# demo_full.net
KiCad netlist of a schematic drawn in EAGLE
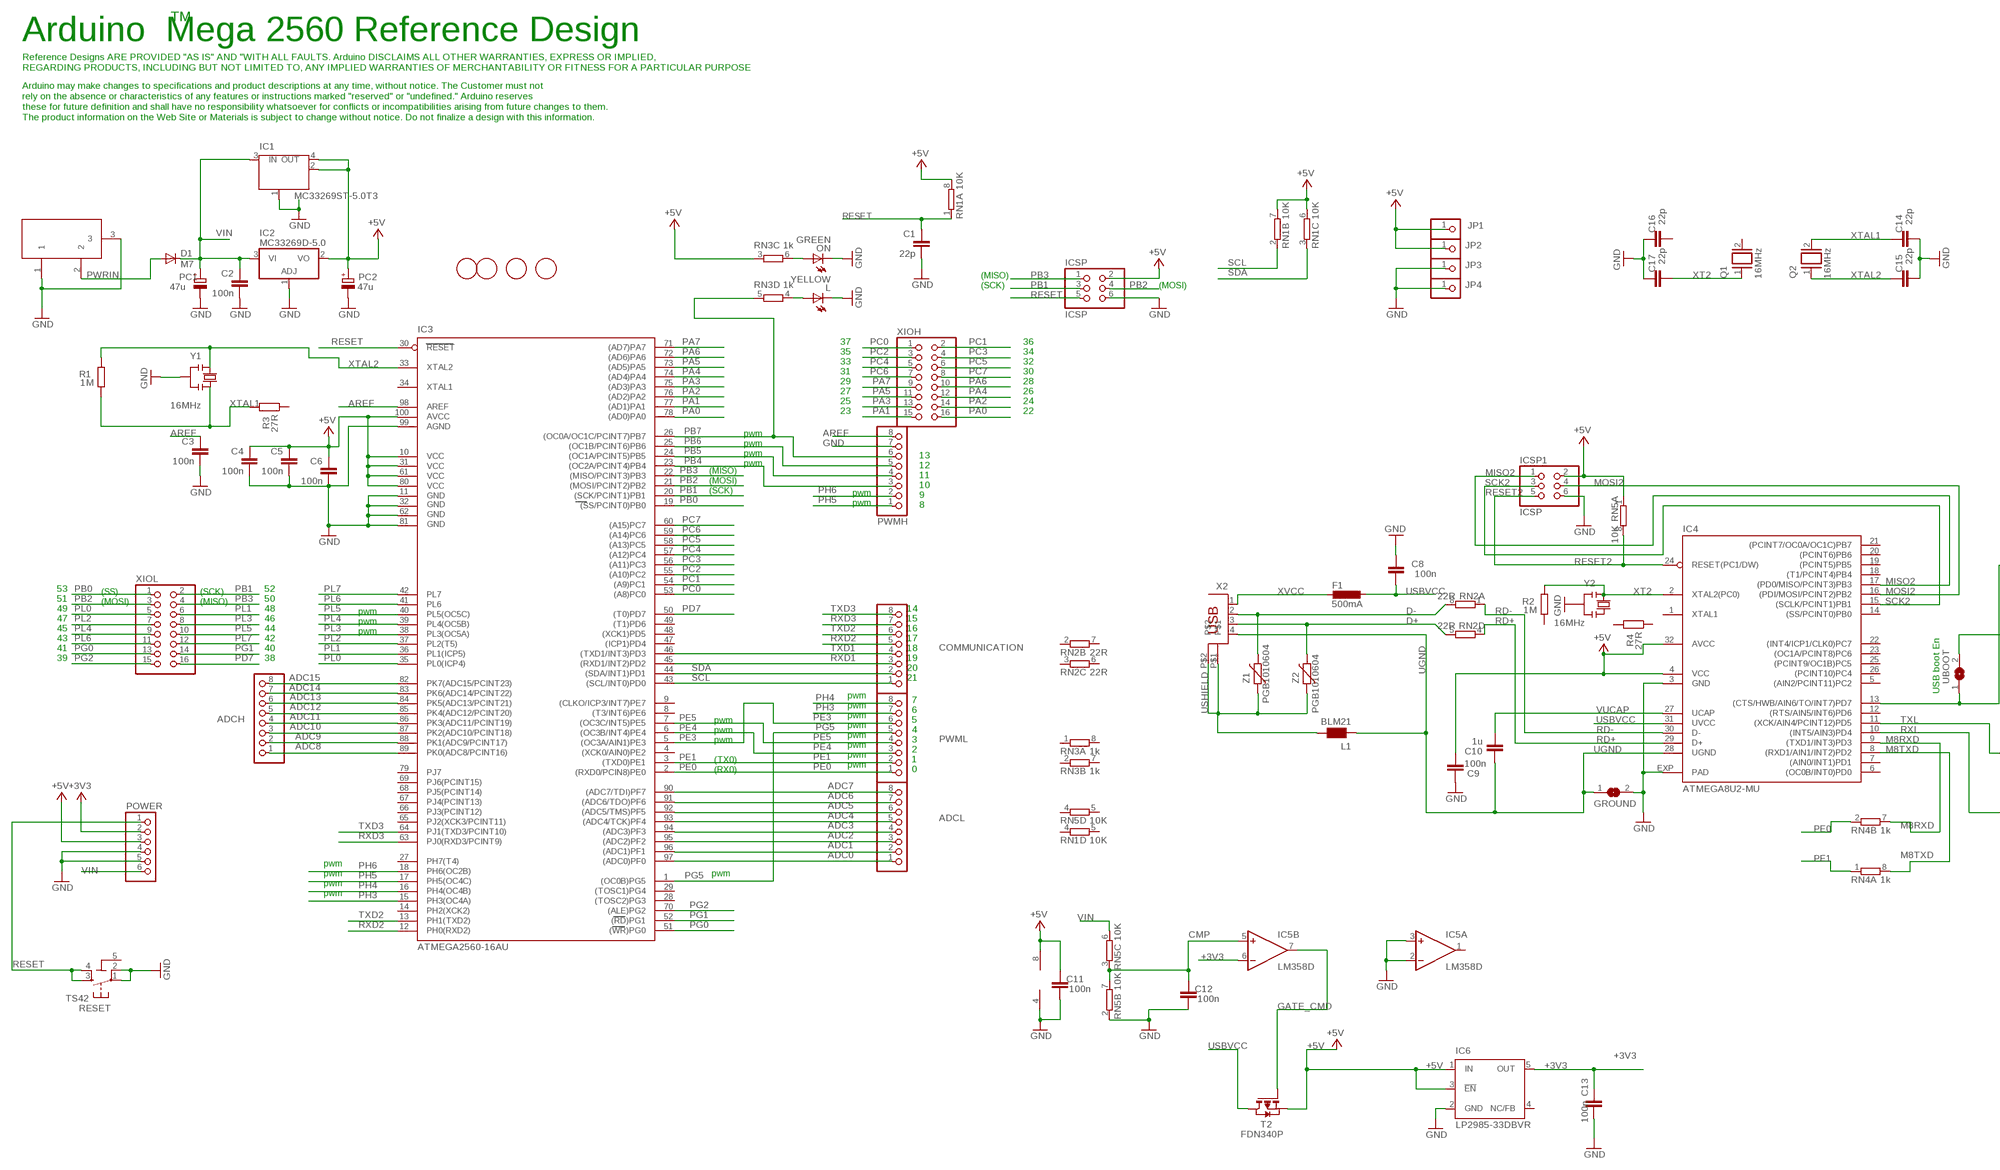
[diagram p0: schematic, sheet 1, part 1 of 2]
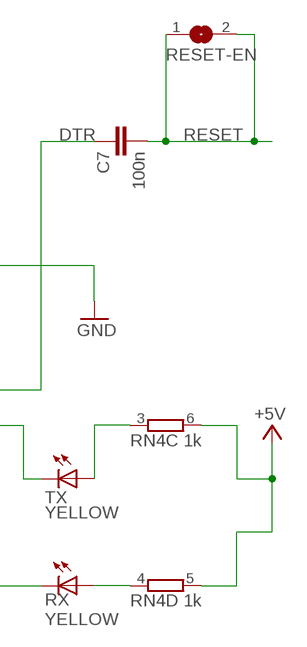
[diagram p1: schematic, sheet 1, part 2 of 2]

(export (version "E")
  (design (tool "Eeschema 10.0.6"))
  (components
    (comp (ref "ADCH")
      (value "PINHD-1X8")
      (footprint "eagle-import:1X08")
      (libsource (lib "eagle-import") (part "PINHD-1X8"))
    )
    (comp (ref "ADCL")
      (value "PINHD-1X8")
      (footprint "eagle-import:1X08")
      (libsource (lib "eagle-import") (part "PINHD-1X8"))
    )
    (comp (ref "C1")
      (value "22p")
      (footprint "eagle-import:C0603-ROUND")
      (libsource (lib "eagle-import") (part "C-EU0603-RND"))
    )
    (comp (ref "C2")
      (value "100n")
      (footprint "eagle-import:C0603-ROUND")
      (libsource (lib "eagle-import") (part "C-EU0603-RND"))
    )
    (comp (ref "C3")
      (value "100n")
      (footprint "eagle-import:C0603-ROUND")
      (libsource (lib "eagle-import") (part "C-EU0603-RND"))
    )
    (comp (ref "C4")
      (value "100n")
      (footprint "eagle-import:C0603-ROUND")
      (libsource (lib "eagle-import") (part "C-EU0603-RND"))
    )
    (comp (ref "C5")
      (value "100n")
      (footprint "eagle-import:C0603-ROUND")
      (libsource (lib "eagle-import") (part "C-EU0603-RND"))
    )
    (comp (ref "C6")
      (value "100n")
      (footprint "eagle-import:C0603-ROUND")
      (libsource (lib "eagle-import") (part "C-EU0603-RND"))
    )
    (comp (ref "C7")
      (value "100n")
      (footprint "eagle-import:C0603-ROUND")
      (libsource (lib "eagle-import") (part "C-EU0603-RND"))
    )
    (comp (ref "C8")
      (value "100n")
      (footprint "eagle-import:C0603")
      (libsource (lib "eagle-import") (part "rcl_C-EUC0603"))
    )
    (comp (ref "C9")
      (value "100n")
      (footprint "eagle-import:C0603-ROUND")
      (libsource (lib "eagle-import") (part "C-EU0603-RND"))
    )
    (comp (ref "C10")
      (value "1u")
      (footprint "eagle-import:C0603-ROUND")
      (libsource (lib "eagle-import") (part "C-EU0603-RND"))
    )
    (comp (ref "C11")
      (value "100n")
      (footprint "eagle-import:C0603")
      (libsource (lib "eagle-import") (part "rcl_C-EUC0603"))
    )
    (comp (ref "C12")
      (value "100n")
      (footprint "eagle-import:C0603-ROUND")
      (libsource (lib "eagle-import") (part "C-EU0603-RND"))
    )
    (comp (ref "C13")
      (value "100n")
      (footprint "eagle-import:C0603-ROUND")
      (libsource (lib "eagle-import") (part "C-EU0603-RND"))
    )
    (comp (ref "C14")
      (value "22p")
      (footprint "eagle-import:C0603-ROUND")
      (libsource (lib "eagle-import") (part "C-EU0603-RND"))
    )
    (comp (ref "C15")
      (value "22p")
      (footprint "eagle-import:C0603-ROUND")
      (libsource (lib "eagle-import") (part "C-EU0603-RND"))
    )
    (comp (ref "C16")
      (value "22p")
      (footprint "eagle-import:C0603-ROUND")
      (libsource (lib "eagle-import") (part "C-EU0603-RND"))
    )
    (comp (ref "C17")
      (value "22p")
      (footprint "eagle-import:C0603-ROUND")
      (libsource (lib "eagle-import") (part "C-EU0603-RND"))
    )
    (comp (ref "COMMUNICATION")
      (value "PINHD-1X8")
      (footprint "eagle-import:1X08")
      (libsource (lib "eagle-import") (part "PINHD-1X8"))
    )
    (comp (ref "D1")
      (value "M7")
      (footprint "eagle-import:SMB")
      (libsource (lib "eagle-import") (part "DIODE-SMB"))
    )
    (comp (ref "F1")
      (value "500mA")
      (footprint "eagle-import:L1812")
      (libsource (lib "eagle-import") (part "L-EUL1812"))
    )
    (comp (ref "GROUND")
      (value "SJ")
      (footprint "eagle-import:SJ")
      (libsource (lib "eagle-import") (part "SJ"))
    )
    (comp (ref "IC1")
      (value "MC33269ST-5.0T3")
      (footprint "eagle-import:SOT223")
      (libsource (lib "eagle-import") (part "MC33269ST-3.3T3"))
    )
    (comp (ref "IC2")
      (value "MC33269D-5.0")
      (footprint "eagle-import:DPACK")
      (libsource (lib "eagle-import") (part "MC33269?D-5.0"))
    )
    (comp (ref "IC3")
      (value "ATMEGA2560-16AU")
      (footprint "eagle-import:TQFP100")
      (libsource (lib "eagle-import") (part "ATMEGAAU1280-16"))
    )
    (comp (ref "IC4")
      (value "ATMEGA8U2-MU")
      (footprint "eagle-import:QFN32")
      (libsource (lib "eagle-import") (part "ATMEGA8U2-MU"))
    )
    (comp (ref "IC5")
      (value "LM358D")
      (footprint "eagle-import:SO08")
      (libsource (lib "eagle-import") (part "LM358D"))
    )
    (comp (ref "IC6")
      (value "LP2985-33DBVR")
      (footprint "eagle-import:SOT23-DBV")
      (libsource (lib "eagle-import") (part "TPS77033"))
    )
    (comp (ref "ICSP")
      (value "ICSP")
      (footprint "eagle-import:2X03")
      (libsource (lib "eagle-import") (part "PINHD-2X3"))
    )
    (comp (ref "ICSP1")
      (value "ICSP")
      (footprint "eagle-import:2X03")
      (libsource (lib "eagle-import") (part "PINHD-2X3"))
    )
    (comp (ref "JP1")
      (value "PINHD-1X1")
      (footprint "eagle-import:1X01")
      (libsource (lib "eagle-import") (part "PINHD-1X1"))
    )
    (comp (ref "JP2")
      (value "PINHD-1X1")
      (footprint "eagle-import:1X01")
      (libsource (lib "eagle-import") (part "PINHD-1X1"))
    )
    (comp (ref "JP3")
      (value "PINHD-1X1")
      (footprint "eagle-import:1X01")
      (libsource (lib "eagle-import") (part "PINHD-1X1"))
    )
    (comp (ref "JP4")
      (value "PINHD-1X1")
      (footprint "eagle-import:1X01")
      (libsource (lib "eagle-import") (part "PINHD-1X1"))
    )
    (comp (ref "L")
      (value "YELLOW")
      (footprint "eagle-import:CHIP-LED0805")
      (libsource (lib "eagle-import") (part "LEDCHIP-LED0805"))
    )
    (comp (ref "L1")
      (value "BLM21")
      (footprint "eagle-import:0805")
      (libsource (lib "eagle-import") (part "WE-CBF_0805"))
    )
    (comp (ref "ON")
      (value "GREEN")
      (footprint "eagle-import:CHIP-LED0805")
      (libsource (lib "eagle-import") (part "LEDCHIP-LED0805"))
    )
    (comp (ref "PC1")
      (value "47u")
      (footprint "eagle-import:PANASONIC_D")
      (libsource (lib "eagle-import") (part "CPOL-EUD"))
    )
    (comp (ref "PC2")
      (value "47u")
      (footprint "eagle-import:PANASONIC_D")
      (libsource (lib "eagle-import") (part "CPOL-EUD"))
    )
    (comp (ref "POWER")
      (value "PINHD-1X6")
      (footprint "eagle-import:1X06")
      (libsource (lib "eagle-import") (part "PINHD-1X6"))
    )
    (comp (ref "PWMH")
      (value "PINHD-1X8")
      (footprint "eagle-import:1X08")
      (libsource (lib "eagle-import") (part "PINHD-1X8"))
    )
    (comp (ref "PWML")
      (value "PINHD-1X8")
      (footprint "eagle-import:1X08")
      (libsource (lib "eagle-import") (part "PINHD-1X8"))
    )
    (comp (ref "Q1")
      (value "16MHz")
      (footprint "eagle-import:QS")
      (libsource (lib "eagle-import") (part "XTAL/S"))
    )
    (comp (ref "Q2")
      (value "16MHz")
      (footprint "eagle-import:QS")
      (libsource (lib "eagle-import") (part "XTAL/S"))
    )
    (comp (ref "R1")
      (value "1M")
      (footprint "eagle-import:R0603-ROUND")
      (libsource (lib "eagle-import") (part "R-EU_R0603"))
    )
    (comp (ref "R2")
      (value "1M")
      (footprint "eagle-import:R0603-ROUND")
      (libsource (lib "eagle-import") (part "R-EU_R0603"))
    )
    (comp (ref "R3")
      (value "27R")
      (footprint "eagle-import:R0603-ROUND")
      (libsource (lib "eagle-import") (part "R-EU_R0603"))
    )
    (comp (ref "R4")
      (value "27R")
      (footprint "eagle-import:R0603-ROUND")
      (libsource (lib "eagle-import") (part "R-EU_R0603"))
    )
    (comp (ref "RESET")
      (value "TS42")
      (footprint "eagle-import:TS42")
      (libsource (lib "eagle-import") (part "TS42"))
    )
    (comp (ref "RESET-EN")
      (value "SJ")
      (footprint "eagle-import:SJ")
      (libsource (lib "eagle-import") (part "SJ"))
    )
    (comp (ref "RN1")
      (value "10K")
      (footprint "eagle-import:CAT16")
      (libsource (lib "eagle-import") (part "4R-NCAT16"))
    )
    (comp (ref "RN2")
      (value "22R")
      (footprint "eagle-import:CAY16")
      (libsource (lib "eagle-import") (part "4R-NCAY16"))
    )
    (comp (ref "RN3")
      (value "1k")
      (footprint "eagle-import:CAY16")
      (libsource (lib "eagle-import") (part "4R-NCAY16"))
    )
    (comp (ref "RN4")
      (value "1k")
      (footprint "eagle-import:CAY16")
      (libsource (lib "eagle-import") (part "4R-NCAY16"))
    )
    (comp (ref "RN5")
      (value "10K")
      (footprint "eagle-import:CAT16")
      (libsource (lib "eagle-import") (part "4R-NCAT16"))
    )
    (comp (ref "RX")
      (value "YELLOW")
      (footprint "eagle-import:CHIP-LED0805")
      (libsource (lib "eagle-import") (part "LEDCHIP-LED0805"))
    )
    (comp (ref "T2")
      (value "FDN340P")
      (footprint "eagle-import:SOT-23")
      (libsource (lib "eagle-import") (part "PMOSSOT23"))
    )
    (comp (ref "TX")
      (value "YELLOW")
      (footprint "eagle-import:CHIP-LED0805")
      (libsource (lib "eagle-import") (part "LEDCHIP-LED0805"))
    )
    (comp (ref "U$2")
      (value "FIDUCIALMOUNT")
      (footprint "eagle-import:FIDUCIA-MOUNT")
      (libsource (lib "eagle-import") (part "FIDUCIALMOUNT"))
    )
    (comp (ref "U$3")
      (value "FIDUCIALMOUNT")
      (footprint "eagle-import:FIDUCIA-MOUNT")
      (libsource (lib "eagle-import") (part "FIDUCIALMOUNT"))
    )
    (comp (ref "U$4")
      (value "FIDUCIALMOUNT")
      (footprint "eagle-import:FIDUCIA-MOUNT")
      (libsource (lib "eagle-import") (part "FIDUCIALMOUNT"))
    )
    (comp (ref "U$5")
      (value "FIDUCIALMOUNT")
      (footprint "eagle-import:FIDUCIA-MOUNT")
      (libsource (lib "eagle-import") (part "FIDUCIALMOUNT"))
    )
    (comp (ref "UBOOT")
      (value "SJ")
      (footprint "eagle-import:SJ")
      (libsource (lib "eagle-import") (part "SJ"))
    )
    (comp (ref "X1")
      (value "DC21MMX")
      (footprint "eagle-import:DC-21MM")
      (libsource (lib "eagle-import") (part "DC21MMX"))
    )
    (comp (ref "X2")
      (value "PN61729")
      (footprint "eagle-import:PN61729")
      (libsource (lib "eagle-import") (part "PN61729"))
    )
    (comp (ref "XIOH")
      (value "PINHD-2X8")
      (footprint "eagle-import:2X08")
      (libsource (lib "eagle-import") (part "PINHD-2X8"))
    )
    (comp (ref "XIOL")
      (value "PINHD-2X8")
      (footprint "eagle-import:2X08")
      (libsource (lib "eagle-import") (part "PINHD-2X8"))
    )
    (comp (ref "Y1")
      (value "16MHz")
      (footprint "eagle-import:RESONATOR")
      (libsource (lib "eagle-import") (part "RESONATORMU"))
    )
    (comp (ref "Y2")
      (value "16MHz")
      (footprint "eagle-import:RESONATOR")
      (libsource (lib "eagle-import") (part "RESONATORMU"))
    )
    (comp (ref "Z1")
      (value "PGB1010604")
      (footprint "eagle-import:CT_CN0603")
      (libsource (lib "eagle-import") (part "VARISTORCN0603"))
    )
    (comp (ref "Z2")
      (value "PGB1010604")
      (footprint "eagle-import:CT_CN0603")
      (libsource (lib "eagle-import") (part "VARISTORCN0603"))
    )
  )
  (nets
    (net (code "1") (name "+3V3") (class "Default")
      (node (ref "C13") (pin "2") (pinfunction "2_2") (pintype "passive"))
      (node (ref "IC5") (pin "6") (pinfunction "-IN_6") (pintype "input"))
      (node (ref "IC6") (pin "5") (pinfunction "OUT_5") (pintype "passive"))
      (node (ref "POWER") (pin "2") (pinfunction "2_2") (pintype "passive"))
    )
    (net (code "2") (name "+5V") (class "Default")
      (node (ref "C11") (pin "2") (pinfunction "2_2") (pintype "passive"))
      (node (ref "C4") (pin "1") (pinfunction "1_1") (pintype "passive"))
      (node (ref "C5") (pin "1") (pinfunction "1_1") (pintype "passive"))
      (node (ref "C6") (pin "1") (pinfunction "1_1") (pintype "passive"))
      (node (ref "C9") (pin "1") (pinfunction "1_1") (pintype "passive"))
      (node (ref "IC1") (pin "2") (pinfunction "OUT_2") (pintype "passive"))
      (node (ref "IC1") (pin "4") (pinfunction "OUT_4") (pintype "passive"))
      (node (ref "IC2") (pin "2") (pinfunction "VO_2") (pintype "passive"))
      (node (ref "IC3") (pin "10") (pinfunction "VCC_10") (pintype "power_in"))
      (node (ref "IC3") (pin "100") (pinfunction "AVCC_100") (pintype "power_in"))
      (node (ref "IC3") (pin "31") (pinfunction "VCC1_31") (pintype "power_in"))
      (node (ref "IC3") (pin "61") (pinfunction "VCC2_61") (pintype "power_in"))
      (node (ref "IC3") (pin "80") (pinfunction "VCC3_80") (pintype "power_in"))
      (node (ref "IC4") (pin "32") (pinfunction "AVCC_32") (pintype "power_in"))
      (node (ref "IC4") (pin "4") (pinfunction "VCC_4") (pintype "power_in"))
      (node (ref "IC5") (pin "8") (pinfunction "V+_8") (pintype "power_in"))
      (node (ref "IC6") (pin "1") (pinfunction "IN_1") (pintype "input"))
      (node (ref "IC6") (pin "3") (pinfunction "~{EN}_3") (pintype "input"))
      (node (ref "ICSP") (pin "2") (pinfunction "2_2") (pintype "passive"))
      (node (ref "ICSP1") (pin "2") (pinfunction "2_2") (pintype "passive"))
      (node (ref "JP1") (pin "1") (pinfunction "1_1") (pintype "passive"))
      (node (ref "JP2") (pin "1") (pinfunction "1_1") (pintype "passive"))
      (node (ref "PC2") (pin "+") (pinfunction "+_+") (pintype "passive"))
      (node (ref "POWER") (pin "3") (pinfunction "3_3") (pintype "passive"))
      (node (ref "RN1") (pin "6") (pinfunction "2_6") (pintype "passive"))
      (node (ref "RN1") (pin "7") (pinfunction "2_7") (pintype "passive"))
      (node (ref "RN1") (pin "8") (pinfunction "2_8") (pintype "passive"))
      (node (ref "RN3") (pin "3") (pinfunction "1_3") (pintype "passive"))
      (node (ref "RN4") (pin "5") (pinfunction "2_5") (pintype "passive"))
      (node (ref "RN4") (pin "6") (pinfunction "2_6") (pintype "passive"))
      (node (ref "RN5") (pin "1") (pinfunction "1_1") (pintype "passive"))
      (node (ref "T2") (pin "2") (pinfunction "S_2") (pintype "passive"))
    )
    (net (code "3") (name "/5-GND") (class "Default")
      (node (ref "RESET") (pin "5") (pinfunction "5-GND_5") (pintype "power_in"))
    )
    (net (code "4") (name "/ADC0") (class "Default")
      (node (ref "ADCL") (pin "1") (pinfunction "1_1") (pintype "passive"))
      (node (ref "IC3") (pin "97") (pinfunction "(ADC0)PF0_97") (pintype "bidirectional"))
    )
    (net (code "5") (name "/ADC1") (class "Default")
      (node (ref "ADCL") (pin "2") (pinfunction "2_2") (pintype "passive"))
      (node (ref "IC3") (pin "96") (pinfunction "(ADC1)PF1_96") (pintype "bidirectional"))
    )
    (net (code "6") (name "/ADC2") (class "Default")
      (node (ref "ADCL") (pin "3") (pinfunction "3_3") (pintype "passive"))
      (node (ref "IC3") (pin "95") (pinfunction "(ADC2)PF2_95") (pintype "bidirectional"))
    )
    (net (code "7") (name "/ADC3") (class "Default")
      (node (ref "ADCL") (pin "4") (pinfunction "4_4") (pintype "passive"))
      (node (ref "IC3") (pin "94") (pinfunction "(ADC3)PF3_94") (pintype "bidirectional"))
    )
    (net (code "8") (name "/ADC4") (class "Default")
      (node (ref "ADCL") (pin "5") (pinfunction "5_5") (pintype "passive"))
      (node (ref "IC3") (pin "93") (pinfunction "(ADC4/TCK)PF4_93") (pintype "bidirectional"))
    )
    (net (code "9") (name "/ADC5") (class "Default")
      (node (ref "ADCL") (pin "6") (pinfunction "6_6") (pintype "passive"))
      (node (ref "IC3") (pin "92") (pinfunction "(ADC5/TMS)PF5_92") (pintype "bidirectional"))
    )
    (net (code "10") (name "/ADC6") (class "Default")
      (node (ref "ADCL") (pin "7") (pinfunction "7_7") (pintype "passive"))
      (node (ref "IC3") (pin "91") (pinfunction "(ADC6/TDO)PF6_91") (pintype "bidirectional"))
    )
    (net (code "11") (name "/ADC7") (class "Default")
      (node (ref "ADCL") (pin "8") (pinfunction "8_8") (pintype "passive"))
      (node (ref "IC3") (pin "90") (pinfunction "(ADC7/TDI)PF7_90") (pintype "bidirectional"))
    )
    (net (code "12") (name "/ADC8") (class "Default")
      (node (ref "ADCH") (pin "1") (pinfunction "1_1") (pintype "passive"))
      (node (ref "IC3") (pin "89") (pinfunction "PK0(ADC8/PCINT16)_89") (pintype "bidirectional"))
    )
    (net (code "13") (name "/ADC9") (class "Default")
      (node (ref "ADCH") (pin "2") (pinfunction "2_2") (pintype "passive"))
      (node (ref "IC3") (pin "88") (pinfunction "PK1(ADC9/PCINT17)_88") (pintype "bidirectional"))
    )
    (net (code "14") (name "/ADC10") (class "Default")
      (node (ref "ADCH") (pin "3") (pinfunction "3_3") (pintype "passive"))
      (node (ref "IC3") (pin "87") (pinfunction "PK2(ADC10/PCINT18)_87") (pintype "bidirectional"))
    )
    (net (code "15") (name "/ADC11") (class "Default")
      (node (ref "ADCH") (pin "4") (pinfunction "4_4") (pintype "passive"))
      (node (ref "IC3") (pin "86") (pinfunction "PK3(ADC11/PCINT19)_86") (pintype "bidirectional"))
    )
    (net (code "16") (name "/ADC12") (class "Default")
      (node (ref "ADCH") (pin "5") (pinfunction "5_5") (pintype "passive"))
      (node (ref "IC3") (pin "85") (pinfunction "PK4(ADC12/PCINT20)_85") (pintype "bidirectional"))
    )
    (net (code "17") (name "/ADC13") (class "Default")
      (node (ref "ADCH") (pin "6") (pinfunction "6_6") (pintype "passive"))
      (node (ref "IC3") (pin "84") (pinfunction "PK5(ADC13/PCINT21)_84") (pintype "bidirectional"))
    )
    (net (code "18") (name "/ADC14") (class "Default")
      (node (ref "ADCH") (pin "7") (pinfunction "7_7") (pintype "passive"))
      (node (ref "IC3") (pin "83") (pinfunction "PK6(ADC14/PCINT22)_83") (pintype "bidirectional"))
    )
    (net (code "19") (name "/ADC15") (class "Default")
      (node (ref "ADCH") (pin "8") (pinfunction "8_8") (pintype "passive"))
      (node (ref "IC3") (pin "82") (pinfunction "PK7(ADC15/PCINT23)_82") (pintype "bidirectional"))
    )
    (net (code "20") (name "/AREF") (class "Default")
      (node (ref "C3") (pin "1") (pinfunction "1_1") (pintype "passive"))
      (node (ref "IC3") (pin "98") (pinfunction "AREF_98") (pintype "bidirectional"))
      (node (ref "PWMH") (pin "8") (pinfunction "8_8") (pintype "passive"))
    )
    (net (code "21") (name "/CMP") (class "Default")
      (node (ref "C12") (pin "2") (pinfunction "2_2") (pintype "passive"))
      (node (ref "IC5") (pin "5") (pinfunction "+IN_5") (pintype "input"))
      (node (ref "RN5") (pin "3") (pinfunction "1_3") (pintype "passive"))
      (node (ref "RN5") (pin "7") (pinfunction "2_7") (pintype "passive"))
    )
    (net (code "22") (name "/D+") (class "Default")
      (node (ref "RN2") (pin "5") (pinfunction "2_5") (pintype "passive"))
      (node (ref "X2") (pin "3") (pinfunction "3_3") (pintype "bidirectional"))
      (node (ref "Z2") (pin "2") (pinfunction "2_2") (pintype "passive"))
    )
    (net (code "23") (name "/D-") (class "Default")
      (node (ref "RN2") (pin "8") (pinfunction "2_8") (pintype "passive"))
      (node (ref "X2") (pin "2") (pinfunction "2_2") (pintype "bidirectional"))
      (node (ref "Z1") (pin "2") (pinfunction "2_2") (pintype "passive"))
    )
    (net (code "24") (name "/DTR") (class "Default")
      (node (ref "C7") (pin "1") (pinfunction "1_1") (pintype "passive"))
      (node (ref "IC4") (pin "13") (pinfunction "(CTS/HWB/AIN6/TO/INT7)PD7_13") (pintype "bidirectional"))
      (node (ref "UBOOT") (pin "1") (pinfunction "1_1") (pintype "passive"))
    )
    (net (code "25") (name "/GATE_CMD") (class "Default")
      (node (ref "IC5") (pin "7") (pinfunction "OUT_7") (pintype "output"))
      (node (ref "T2") (pin "3") (pinfunction "G_3") (pintype "passive"))
    )
    (net (code "26") (name "/M8RXD") (class "Default")
      (node (ref "IC4") (pin "9") (pinfunction "(TXD1/INT3)PD3_9") (pintype "bidirectional"))
      (node (ref "RN4") (pin "7") (pinfunction "2_7") (pintype "passive"))
    )
    (net (code "27") (name "/M8TXD") (class "Default")
      (node (ref "IC4") (pin "8") (pinfunction "(RXD1/AIN1/INT2)PD2_8") (pintype "bidirectional"))
      (node (ref "RN4") (pin "8") (pinfunction "2_8") (pintype "passive"))
    )
    (net (code "28") (name "/MISO2") (class "Default")
      (node (ref "IC4") (pin "17") (pinfunction "(PD0/MISO/PCINT3)PB3_17") (pintype "bidirectional"))
      (node (ref "ICSP1") (pin "1") (pinfunction "1_1") (pintype "passive"))
    )
    (net (code "29") (name "/MOSI2") (class "Default")
      (node (ref "IC4") (pin "16") (pinfunction "(PDI/MOSI/PCINT2)PB2_16") (pintype "bidirectional"))
      (node (ref "ICSP1") (pin "4") (pinfunction "4_4") (pintype "passive"))
    )
    (net (code "30") (name "/PA0") (class "Default")
      (node (ref "IC3") (pin "78") (pinfunction "(AD0)PA0_78") (pintype "bidirectional"))
      (node (ref "XIOH") (pin "16") (pinfunction "16_16") (pintype "passive"))
    )
    (net (code "31") (name "/PA1") (class "Default")
      (node (ref "IC3") (pin "77") (pinfunction "(AD1)PA1_77") (pintype "bidirectional"))
      (node (ref "XIOH") (pin "15") (pinfunction "15_15") (pintype "passive"))
    )
    (net (code "32") (name "/PA2") (class "Default")
      (node (ref "IC3") (pin "76") (pinfunction "(AD2)PA2_76") (pintype "bidirectional"))
      (node (ref "XIOH") (pin "14") (pinfunction "14_14") (pintype "passive"))
    )
    (net (code "33") (name "/PA3") (class "Default")
      (node (ref "IC3") (pin "75") (pinfunction "(AD3)PA3_75") (pintype "bidirectional"))
      (node (ref "XIOH") (pin "13") (pinfunction "13_13") (pintype "passive"))
    )
    (net (code "34") (name "/PA4") (class "Default")
      (node (ref "IC3") (pin "74") (pinfunction "(AD4)PA4_74") (pintype "bidirectional"))
      (node (ref "XIOH") (pin "12") (pinfunction "12_12") (pintype "passive"))
    )
    (net (code "35") (name "/PA5") (class "Default")
      (node (ref "IC3") (pin "73") (pinfunction "(AD5)PA5_73") (pintype "bidirectional"))
      (node (ref "XIOH") (pin "11") (pinfunction "11_11") (pintype "passive"))
    )
    (net (code "36") (name "/PA6") (class "Default")
      (node (ref "IC3") (pin "72") (pinfunction "(AD6)PA6_72") (pintype "bidirectional"))
      (node (ref "XIOH") (pin "10") (pinfunction "10_10") (pintype "passive"))
    )
    (net (code "37") (name "/PA7") (class "Default")
      (node (ref "IC3") (pin "71") (pinfunction "(AD7)PA7_71") (pintype "bidirectional"))
      (node (ref "XIOH") (pin "9") (pinfunction "9_9") (pintype "passive"))
    )
    (net (code "38") (name "/PB0") (class "Default")
      (node (ref "IC3") (pin "19") (pinfunction "(SS/PCINT0)PB0_19") (pintype "bidirectional"))
      (node (ref "XIOL") (pin "1") (pinfunction "1_1") (pintype "passive"))
    )
    (net (code "39") (name "/PB1") (class "Default")
      (node (ref "IC3") (pin "20") (pinfunction "(SCK/PCINT1)PB1_20") (pintype "bidirectional"))
      (node (ref "ICSP") (pin "3") (pinfunction "3_3") (pintype "passive"))
      (node (ref "XIOL") (pin "2") (pinfunction "2_2") (pintype "passive"))
    )
    (net (code "40") (name "/PB2") (class "Default")
      (node (ref "IC3") (pin "21") (pinfunction "(MOSI/PCINT2)PB2_21") (pintype "bidirectional"))
      (node (ref "ICSP") (pin "4") (pinfunction "4_4") (pintype "passive"))
      (node (ref "XIOL") (pin "3") (pinfunction "3_3") (pintype "passive"))
    )
    (net (code "41") (name "/PB3") (class "Default")
      (node (ref "IC3") (pin "22") (pinfunction "(MISO/PCINT3)PB3_22") (pintype "bidirectional"))
      (node (ref "ICSP") (pin "1") (pinfunction "1_1") (pintype "passive"))
      (node (ref "XIOL") (pin "4") (pinfunction "4_4") (pintype "passive"))
    )
    (net (code "42") (name "/PB4") (class "Default")
      (node (ref "IC3") (pin "23") (pinfunction "(OC2A/PCINT4)PB4_23") (pintype "bidirectional"))
      (node (ref "PWMH") (pin "3") (pinfunction "3_3") (pintype "passive"))
    )
    (net (code "43") (name "/PB5") (class "Default")
      (node (ref "IC3") (pin "24") (pinfunction "(OC1A/PCINT5)PB5_24") (pintype "bidirectional"))
      (node (ref "PWMH") (pin "4") (pinfunction "4_4") (pintype "passive"))
    )
    (net (code "44") (name "/PB6") (class "Default")
      (node (ref "IC3") (pin "25") (pinfunction "(OC1B/PCINT6)PB6_25") (pintype "bidirectional"))
      (node (ref "PWMH") (pin "5") (pinfunction "5_5") (pintype "passive"))
    )
    (net (code "45") (name "/PB7") (class "Default")
      (node (ref "IC3") (pin "26") (pinfunction "(OC0A/OC1C/PCINT7)PB7_26") (pintype "bidirectional"))
      (node (ref "PWMH") (pin "6") (pinfunction "6_6") (pintype "passive"))
      (node (ref "RN3") (pin "5") (pinfunction "2_5") (pintype "passive"))
    )
    (net (code "46") (name "/PC0") (class "Default")
      (node (ref "IC3") (pin "53") (pinfunction "(A8)PC0_53") (pintype "bidirectional"))
      (node (ref "XIOH") (pin "1") (pinfunction "1_1") (pintype "passive"))
    )
    (net (code "47") (name "/PC1") (class "Default")
      (node (ref "IC3") (pin "54") (pinfunction "(A9)PC1_54") (pintype "bidirectional"))
      (node (ref "XIOH") (pin "2") (pinfunction "2_2") (pintype "passive"))
    )
    (net (code "48") (name "/PC2") (class "Default")
      (node (ref "IC3") (pin "55") (pinfunction "(A10)PC2_55") (pintype "bidirectional"))
      (node (ref "XIOH") (pin "3") (pinfunction "3_3") (pintype "passive"))
    )
    (net (code "49") (name "/PC3") (class "Default")
      (node (ref "IC3") (pin "56") (pinfunction "(A11)PC3_56") (pintype "bidirectional"))
      (node (ref "XIOH") (pin "4") (pinfunction "4_4") (pintype "passive"))
    )
    (net (code "50") (name "/PC4") (class "Default")
      (node (ref "IC3") (pin "57") (pinfunction "(A12)PC4_57") (pintype "bidirectional"))
      (node (ref "XIOH") (pin "5") (pinfunction "5_5") (pintype "passive"))
    )
    (net (code "51") (name "/PC5") (class "Default")
      (node (ref "IC3") (pin "58") (pinfunction "(A13)PC5_58") (pintype "bidirectional"))
      (node (ref "XIOH") (pin "6") (pinfunction "6_6") (pintype "passive"))
    )
    (net (code "52") (name "/PC6") (class "Default")
      (node (ref "IC3") (pin "59") (pinfunction "(A14)PC6_59") (pintype "bidirectional"))
      (node (ref "XIOH") (pin "7") (pinfunction "7_7") (pintype "passive"))
    )
    (net (code "53") (name "/PC7") (class "Default")
      (node (ref "IC3") (pin "60") (pinfunction "(A15)PC7_60") (pintype "bidirectional"))
      (node (ref "XIOH") (pin "8") (pinfunction "8_8") (pintype "passive"))
    )
    (net (code "54") (name "/PD7") (class "Default")
      (node (ref "IC3") (pin "50") (pinfunction "(T0)PD7_50") (pintype "bidirectional"))
      (node (ref "XIOL") (pin "16") (pinfunction "16_16") (pintype "passive"))
    )
    (net (code "55") (name "/PE0") (class "Default")
      (node (ref "IC3") (pin "2") (pinfunction "(RXD0/PCIN8)PE0_2") (pintype "bidirectional"))
      (node (ref "PWML") (pin "1") (pinfunction "1_1") (pintype "passive"))
      (node (ref "RN4") (pin "2") (pinfunction "1_2") (pintype "passive"))
    )
    (net (code "56") (name "/PE1") (class "Default")
      (node (ref "IC3") (pin "3") (pinfunction "(TXD0)PE1_3") (pintype "bidirectional"))
      (node (ref "PWML") (pin "2") (pinfunction "2_2") (pintype "passive"))
      (node (ref "RN4") (pin "1") (pinfunction "1_1") (pintype "passive"))
    )
    (net (code "57") (name "/PE3") (class "Default")
      (node (ref "IC3") (pin "5") (pinfunction "(OC3A/AIN1)PE3_5") (pintype "bidirectional"))
      (node (ref "PWML") (pin "6") (pinfunction "6_6") (pintype "passive"))
    )
    (net (code "58") (name "/PE4") (class "Default")
      (node (ref "IC3") (pin "6") (pinfunction "(OC3B/INT4)PE4_6") (pintype "bidirectional"))
      (node (ref "PWML") (pin "3") (pinfunction "3_3") (pintype "passive"))
    )
    (net (code "59") (name "/PE5") (class "Default")
      (node (ref "IC3") (pin "7") (pinfunction "(OC3C/INT5)PE5_7") (pintype "bidirectional"))
      (node (ref "PWML") (pin "4") (pinfunction "4_4") (pintype "passive"))
    )
    (net (code "60") (name "/PG0") (class "Default")
      (node (ref "IC3") (pin "51") (pinfunction "(WR)PG0_51") (pintype "bidirectional"))
      (node (ref "XIOL") (pin "13") (pinfunction "13_13") (pintype "passive"))
    )
    (net (code "61") (name "/PG1") (class "Default")
      (node (ref "IC3") (pin "52") (pinfunction "(RD)PG1_52") (pintype "bidirectional"))
      (node (ref "XIOL") (pin "14") (pinfunction "14_14") (pintype "passive"))
    )
    (net (code "62") (name "/PG2") (class "Default")
      (node (ref "IC3") (pin "70") (pinfunction "(ALE)PG2_70") (pintype "bidirectional"))
      (node (ref "XIOL") (pin "15") (pinfunction "15_15") (pintype "passive"))
    )
    (net (code "63") (name "/PG5") (class "Default")
      (node (ref "IC3") (pin "1") (pinfunction "(OC0B)PG5_1") (pintype "bidirectional"))
      (node (ref "PWML") (pin "5") (pinfunction "5_5") (pintype "passive"))
    )
    (net (code "64") (name "/PH3") (class "Default")
      (node (ref "IC3") (pin "15") (pinfunction "PH3(OC4A)_15") (pintype "bidirectional"))
      (node (ref "PWML") (pin "7") (pinfunction "7_7") (pintype "passive"))
    )
    (net (code "65") (name "/PH4") (class "Default")
      (node (ref "IC3") (pin "16") (pinfunction "PH4(OC4B)_16") (pintype "bidirectional"))
      (node (ref "PWML") (pin "8") (pinfunction "8_8") (pintype "passive"))
    )
    (net (code "66") (name "/PH5") (class "Default")
      (node (ref "IC3") (pin "17") (pinfunction "PH5(OC4C)_17") (pintype "bidirectional"))
      (node (ref "PWMH") (pin "1") (pinfunction "1_1") (pintype "passive"))
    )
    (net (code "67") (name "/PH6") (class "Default")
      (node (ref "IC3") (pin "18") (pinfunction "PH6(OC2B)_18") (pintype "bidirectional"))
      (node (ref "PWMH") (pin "2") (pinfunction "2_2") (pintype "passive"))
    )
    (net (code "68") (name "/PL0") (class "Default")
      (node (ref "IC3") (pin "35") (pinfunction "PL0(ICP4)_35") (pintype "bidirectional"))
      (node (ref "XIOL") (pin "5") (pinfunction "5_5") (pintype "passive"))
    )
    (net (code "69") (name "/PL1") (class "Default")
      (node (ref "IC3") (pin "36") (pinfunction "PL1(ICP5)_36") (pintype "bidirectional"))
      (node (ref "XIOL") (pin "6") (pinfunction "6_6") (pintype "passive"))
    )
    (net (code "70") (name "/PL2") (class "Default")
      (node (ref "IC3") (pin "37") (pinfunction "PL2(T5)_37") (pintype "bidirectional"))
      (node (ref "XIOL") (pin "7") (pinfunction "7_7") (pintype "passive"))
    )
    (net (code "71") (name "/PL3") (class "Default")
      (node (ref "IC3") (pin "38") (pinfunction "PL3(OC5A)_38") (pintype "bidirectional"))
      (node (ref "XIOL") (pin "8") (pinfunction "8_8") (pintype "passive"))
    )
    (net (code "72") (name "/PL4") (class "Default")
      (node (ref "IC3") (pin "39") (pinfunction "PL4(OC5B)_39") (pintype "bidirectional"))
      (node (ref "XIOL") (pin "9") (pinfunction "9_9") (pintype "passive"))
    )
    (net (code "73") (name "/PL5") (class "Default")
      (node (ref "IC3") (pin "40") (pinfunction "PL5(OC5C)_40") (pintype "bidirectional"))
      (node (ref "XIOL") (pin "10") (pinfunction "10_10") (pintype "passive"))
    )
    (net (code "74") (name "/PL6") (class "Default")
      (node (ref "IC3") (pin "41") (pinfunction "PL6_41") (pintype "bidirectional"))
      (node (ref "XIOL") (pin "11") (pinfunction "11_11") (pintype "passive"))
    )
    (net (code "75") (name "/PL7") (class "Default")
      (node (ref "IC3") (pin "42") (pinfunction "PL7_42") (pintype "bidirectional"))
      (node (ref "XIOL") (pin "12") (pinfunction "12_12") (pintype "passive"))
    )
    (net (code "76") (name "/PWRIN") (class "Default")
      (node (ref "D1") (pin "A") (pinfunction "A_A") (pintype "passive"))
      (node (ref "X1") (pin "2") (pinfunction "2_2") (pintype "power_in"))
    )
    (net (code "77") (name "/RD+") (class "Default")
      (node (ref "IC4") (pin "29") (pinfunction "D+_29") (pintype "bidirectional"))
      (node (ref "RN2") (pin "4") (pinfunction "1_4") (pintype "passive"))
    )
    (net (code "78") (name "/RD-") (class "Default")
      (node (ref "IC4") (pin "30") (pinfunction "D-_30") (pintype "bidirectional"))
      (node (ref "RN2") (pin "1") (pinfunction "1_1") (pintype "passive"))
    )
    (net (code "79") (name "/RESET") (class "Default")
      (node (ref "C1") (pin "1") (pinfunction "1_1") (pintype "passive"))
      (node (ref "C7") (pin "2") (pinfunction "2_2") (pintype "passive"))
      (node (ref "IC3") (pin "30") (pinfunction "RESET_30") (pintype "input"))
      (node (ref "ICSP") (pin "5") (pinfunction "5_5") (pintype "passive"))
      (node (ref "POWER") (pin "1") (pinfunction "1_1") (pintype "passive"))
      (node (ref "RESET") (pin "3") (pinfunction "3_3") (pintype "passive"))
      (node (ref "RESET") (pin "4") (pinfunction "4_4") (pintype "passive"))
      (node (ref "RESET-EN") (pin "1") (pinfunction "1_1") (pintype "passive"))
      (node (ref "RESET-EN") (pin "2") (pinfunction "2_2") (pintype "passive"))
      (node (ref "RN1") (pin "1") (pinfunction "1_1") (pintype "passive"))
    )
    (net (code "80") (name "/RESET2") (class "Default")
      (node (ref "IC4") (pin "24") (pinfunction "RESET(PC1/DW)_24") (pintype "input"))
      (node (ref "ICSP1") (pin "5") (pinfunction "5_5") (pintype "passive"))
      (node (ref "RN5") (pin "8") (pinfunction "2_8") (pintype "passive"))
    )
    (net (code "81") (name "/RXD1") (class "Default")
      (node (ref "COMMUNICATION") (pin "3") (pinfunction "3_3") (pintype "passive"))
      (node (ref "IC3") (pin "45") (pinfunction "(RXD1/INT2)PD2_45") (pintype "bidirectional"))
    )
    (net (code "82") (name "/RXD2") (class "Default")
      (node (ref "COMMUNICATION") (pin "5") (pinfunction "5_5") (pintype "passive"))
      (node (ref "IC3") (pin "12") (pinfunction "PH0(RXD2)_12") (pintype "bidirectional"))
    )
    (net (code "83") (name "/RXD3") (class "Default")
      (node (ref "COMMUNICATION") (pin "7") (pinfunction "7_7") (pintype "passive"))
      (node (ref "IC3") (pin "63") (pinfunction "PJ0(RXD3/PCINT9)_63") (pintype "bidirectional"))
    )
    (net (code "84") (name "/RXL") (class "Default")
      (node (ref "IC4") (pin "10") (pinfunction "(INT5/AIN3)PD4_10") (pintype "bidirectional"))
      (node (ref "RX") (pin "C") (pinfunction "C_C") (pintype "passive"))
    )
    (net (code "85") (name "/SCK2") (class "Default")
      (node (ref "IC4") (pin "15") (pinfunction "(SCLK/PCINT1)PB1_15") (pintype "bidirectional"))
      (node (ref "ICSP1") (pin "3") (pinfunction "3_3") (pintype "passive"))
    )
    (net (code "86") (name "/SCL") (class "Default")
      (node (ref "COMMUNICATION") (pin "1") (pinfunction "1_1") (pintype "passive"))
      (node (ref "IC3") (pin "43") (pinfunction "(SCL/INT0)PD0_43") (pintype "bidirectional"))
      (node (ref "RN1") (pin "2") (pinfunction "1_2") (pintype "passive"))
    )
    (net (code "87") (name "/SDA") (class "Default")
      (node (ref "COMMUNICATION") (pin "2") (pinfunction "2_2") (pintype "passive"))
      (node (ref "IC3") (pin "44") (pinfunction "(SDA/INT1)PD1_44") (pintype "bidirectional"))
      (node (ref "RN1") (pin "3") (pinfunction "1_3") (pintype "passive"))
    )
    (net (code "88") (name "/TXD1") (class "Default")
      (node (ref "COMMUNICATION") (pin "4") (pinfunction "4_4") (pintype "passive"))
      (node (ref "IC3") (pin "46") (pinfunction "(TXD1/INT3)PD3_46") (pintype "bidirectional"))
    )
    (net (code "89") (name "/TXD2") (class "Default")
      (node (ref "COMMUNICATION") (pin "6") (pinfunction "6_6") (pintype "passive"))
      (node (ref "IC3") (pin "13") (pinfunction "PH1(TXD2)_13") (pintype "bidirectional"))
    )
    (net (code "90") (name "/TXD3") (class "Default")
      (node (ref "COMMUNICATION") (pin "8") (pinfunction "8_8") (pintype "passive"))
      (node (ref "IC3") (pin "64") (pinfunction "PJ1(TXD3/PCINT10)_64") (pintype "bidirectional"))
    )
    (net (code "91") (name "/TXL") (class "Default")
      (node (ref "IC4") (pin "11") (pinfunction "(XCK/AIN4/PCINT12)PD5_11") (pintype "bidirectional"))
      (node (ref "TX") (pin "C") (pinfunction "C_C") (pintype "passive"))
    )
    (net (code "92") (name "/UGND") (class "Default")
      (node (ref "C10") (pin "2") (pinfunction "2_2") (pintype "passive"))
      (node (ref "GROUND") (pin "1") (pinfunction "1_1") (pintype "passive"))
      (node (ref "IC4") (pin "28") (pinfunction "UGND_28") (pintype "power_in"))
      (node (ref "L1") (pin "1") (pinfunction "1_1") (pintype "passive"))
      (node (ref "X2") (pin "4") (pinfunction "4_4") (pintype "bidirectional"))
    )
    (net (code "93") (name "/USBVCC") (class "Default")
      (node (ref "C8") (pin "1") (pinfunction "1_1") (pintype "passive"))
      (node (ref "F1") (pin "1") (pinfunction "1_1") (pintype "passive"))
      (node (ref "IC4") (pin "31") (pinfunction "UVCC_31") (pintype "power_in"))
      (node (ref "T2") (pin "1") (pinfunction "D_1") (pintype "passive"))
    )
    (net (code "94") (name "/USHIELD") (class "Default")
      (node (ref "L1") (pin "2") (pinfunction "2_2") (pintype "passive"))
      (node (ref "X2") (pin "P$1") (pinfunction "P$1_P$1") (pintype "bidirectional"))
      (node (ref "X2") (pin "P$2") (pinfunction "P$2_P$2") (pintype "bidirectional"))
      (node (ref "Z1") (pin "1") (pinfunction "1_1") (pintype "passive"))
      (node (ref "Z2") (pin "1") (pinfunction "1_1") (pintype "passive"))
    )
    (net (code "95") (name "/VIN") (class "Default")
      (node (ref "C2") (pin "1") (pinfunction "1_1") (pintype "passive"))
      (node (ref "D1") (pin "C") (pinfunction "C_C") (pintype "passive"))
      (node (ref "IC1") (pin "3") (pinfunction "IN_3") (pintype "input"))
      (node (ref "IC2") (pin "3") (pinfunction "VI_3") (pintype "input"))
      (node (ref "PC1") (pin "+") (pinfunction "+_+") (pintype "passive"))
      (node (ref "POWER") (pin "6") (pinfunction "6_6") (pintype "passive"))
      (node (ref "RN5") (pin "6") (pinfunction "2_6") (pintype "passive"))
    )
    (net (code "96") (name "/VUCAP") (class "Default")
      (node (ref "C10") (pin "1") (pinfunction "1_1") (pintype "passive"))
      (node (ref "IC4") (pin "27") (pinfunction "UCAP_27") (pintype "passive"))
    )
    (net (code "97") (name "/XT2") (class "Default")
      (node (ref "C17") (pin "1") (pinfunction "1_1") (pintype "passive"))
      (node (ref "IC4") (pin "2") (pinfunction "XTAL2(PC0)_2") (pintype "bidirectional"))
      (node (ref "Q1") (pin "1") (pinfunction "1_1") (pintype "passive"))
      (node (ref "R2") (pin "2") (pinfunction "2_2") (pintype "passive"))
      (node (ref "Y2") (pin "1") (pinfunction "1_1") (pintype "passive"))
    )
    (net (code "98") (name "/XTAL1") (class "Default")
      (node (ref "C14") (pin "2") (pinfunction "2_2") (pintype "passive"))
      (node (ref "Q2") (pin "2") (pinfunction "2_2") (pintype "passive"))
      (node (ref "R1") (pin "1") (pinfunction "1_1") (pintype "passive"))
      (node (ref "R3") (pin "2") (pinfunction "2_2") (pintype "passive"))
      (node (ref "Y1") (pin "3") (pinfunction "3_3") (pintype "passive"))
    )
    (net (code "99") (name "/XTAL2") (class "Default")
      (node (ref "C15") (pin "2") (pinfunction "2_2") (pintype "passive"))
      (node (ref "IC3") (pin "33") (pinfunction "XTAL2_33") (pintype "output"))
      (node (ref "Q2") (pin "1") (pinfunction "1_1") (pintype "passive"))
      (node (ref "R1") (pin "2") (pinfunction "2_2") (pintype "passive"))
      (node (ref "Y1") (pin "1") (pinfunction "1_1") (pintype "passive"))
    )
    (net (code "100") (name "/XVCC") (class "Default")
      (node (ref "F1") (pin "2") (pinfunction "2_2") (pintype "passive"))
      (node (ref "X2") (pin "1") (pinfunction "1_1") (pintype "bidirectional"))
    )
    (net (code "101") (name "GND") (class "Default")
      (node (ref "C1") (pin "2") (pinfunction "2_2") (pintype "passive"))
      (node (ref "C11") (pin "1") (pinfunction "1_1") (pintype "passive"))
      (node (ref "C12") (pin "1") (pinfunction "1_1") (pintype "passive"))
      (node (ref "C13") (pin "1") (pinfunction "1_1") (pintype "passive"))
      (node (ref "C14") (pin "1") (pinfunction "1_1") (pintype "passive"))
      (node (ref "C15") (pin "1") (pinfunction "1_1") (pintype "passive"))
      (node (ref "C16") (pin "2") (pinfunction "2_2") (pintype "passive"))
      (node (ref "C17") (pin "2") (pinfunction "2_2") (pintype "passive"))
      (node (ref "C2") (pin "2") (pinfunction "2_2") (pintype "passive"))
      (node (ref "C3") (pin "2") (pinfunction "2_2") (pintype "passive"))
      (node (ref "C4") (pin "2") (pinfunction "2_2") (pintype "passive"))
      (node (ref "C5") (pin "2") (pinfunction "2_2") (pintype "passive"))
      (node (ref "C6") (pin "2") (pinfunction "2_2") (pintype "passive"))
      (node (ref "C8") (pin "2") (pinfunction "2_2") (pintype "passive"))
      (node (ref "C9") (pin "2") (pinfunction "2_2") (pintype "passive"))
      (node (ref "GROUND") (pin "2") (pinfunction "2_2") (pintype "passive"))
      (node (ref "IC1") (pin "1") (pinfunction "GND/ADJ_1") (pintype "input"))
      (node (ref "IC2") (pin "1") (pinfunction "ADJ_1") (pintype "input"))
      (node (ref "IC3") (pin "11") (pinfunction "GND_11") (pintype "power_in"))
      (node (ref "IC3") (pin "32") (pinfunction "GND1_32") (pintype "power_in"))
      (node (ref "IC3") (pin "62") (pinfunction "GND2_62") (pintype "power_in"))
      (node (ref "IC3") (pin "81") (pinfunction "GND3_81") (pintype "power_in"))
      (node (ref "IC3") (pin "99") (pinfunction "AGND_99") (pintype "power_in"))
      (node (ref "IC4") (pin "3") (pinfunction "GND_3") (pintype "power_in"))
      (node (ref "IC4") (pin "EXP") (pinfunction "PAD_EXP") (pintype "power_in"))
      (node (ref "IC5") (pin "2") (pinfunction "-IN_2") (pintype "input"))
      (node (ref "IC5") (pin "3") (pinfunction "+IN_3") (pintype "input"))
      (node (ref "IC5") (pin "4") (pinfunction "V-_4") (pintype "power_in"))
      (node (ref "IC6") (pin "2") (pinfunction "GND_2") (pintype "power_in"))
      (node (ref "ICSP") (pin "6") (pinfunction "6_6") (pintype "passive"))
      (node (ref "ICSP1") (pin "6") (pinfunction "6_6") (pintype "passive"))
      (node (ref "JP3") (pin "1") (pinfunction "1_1") (pintype "passive"))
      (node (ref "JP4") (pin "1") (pinfunction "1_1") (pintype "passive"))
      (node (ref "L") (pin "C") (pinfunction "C_C") (pintype "passive"))
      (node (ref "ON") (pin "C") (pinfunction "C_C") (pintype "passive"))
      (node (ref "PC1") (pin "-") (pinfunction "-_-") (pintype "passive"))
      (node (ref "PC2") (pin "-") (pinfunction "-_-") (pintype "passive"))
      (node (ref "POWER") (pin "4") (pinfunction "4_4") (pintype "passive"))
      (node (ref "POWER") (pin "5") (pinfunction "5_5") (pintype "passive"))
      (node (ref "PWMH") (pin "7") (pinfunction "7_7") (pintype "passive"))
      (node (ref "RESET") (pin "1") (pinfunction "1_1") (pintype "passive"))
      (node (ref "RESET") (pin "2") (pinfunction "2_2") (pintype "passive"))
      (node (ref "RN5") (pin "2") (pinfunction "1_2") (pintype "passive"))
      (node (ref "UBOOT") (pin "2") (pinfunction "2_2") (pintype "passive"))
      (node (ref "X1") (pin "1") (pinfunction "1_1") (pintype "power_in"))
      (node (ref "X1") (pin "3") (pinfunction "3_3") (pintype "power_in"))
      (node (ref "Y1") (pin "2") (pinfunction "2_2") (pintype "passive"))
      (node (ref "Y2") (pin "2") (pinfunction "2_2") (pintype "passive"))
    )
    (net (code "102") (name "Net-(RN3C-2)") (class "Default")
      (node (ref "ON") (pin "A") (pinfunction "A_A") (pintype "passive"))
      (node (ref "RN3") (pin "6") (pinfunction "2_6") (pintype "passive"))
    )
    (net (code "103") (name "Net-(RN3D-1)") (class "Default")
      (node (ref "L") (pin "A") (pinfunction "A_A") (pintype "passive"))
      (node (ref "RN3") (pin "4") (pinfunction "1_4") (pintype "passive"))
    )
    (net (code "104") (name "Net-(RN4C-1)") (class "Default")
      (node (ref "RN4") (pin "3") (pinfunction "1_3") (pintype "passive"))
      (node (ref "TX") (pin "A") (pinfunction "A_A") (pintype "passive"))
    )
    (net (code "105") (name "Net-(RN4D-1)") (class "Default")
      (node (ref "RN4") (pin "4") (pinfunction "1_4") (pintype "passive"))
      (node (ref "RX") (pin "A") (pinfunction "A_A") (pintype "passive"))
    )
    (net (code "106") (name "unconnected-(C16-Pad1)") (class "Default")
      (node (ref "C16") (pin "1") (pinfunction "1_1") (pintype "passive"))
    )
    (net (code "107") (name "unconnected-(IC3-(CLKO{slash}ICP3{slash}INT7)PE7-Pad9)") (class "Default")
      (node (ref "IC3") (pin "9") (pinfunction "(CLKO/ICP3/INT7)PE7_9") (pintype "bidirectional"))
    )
    (net (code "108") (name "unconnected-(IC3-(ICP1)PD4-Pad47)") (class "Default")
      (node (ref "IC3") (pin "47") (pinfunction "(ICP1)PD4_47") (pintype "bidirectional"))
    )
    (net (code "109") (name "unconnected-(IC3-(T1)PD6-Pad49)") (class "Default")
      (node (ref "IC3") (pin "49") (pinfunction "(T1)PD6_49") (pintype "bidirectional"))
    )
    (net (code "110") (name "unconnected-(IC3-(T3{slash}INT6)PE6-Pad8)") (class "Default")
      (node (ref "IC3") (pin "8") (pinfunction "(T3/INT6)PE6_8") (pintype "bidirectional"))
    )
    (net (code "111") (name "unconnected-(IC3-(TOSC1)PG4-Pad29)") (class "Default")
      (node (ref "IC3") (pin "29") (pinfunction "(TOSC1)PG4_29") (pintype "bidirectional"))
    )
    (net (code "112") (name "unconnected-(IC3-(TOSC2)PG3-Pad28)") (class "Default")
      (node (ref "IC3") (pin "28") (pinfunction "(TOSC2)PG3_28") (pintype "bidirectional"))
    )
    (net (code "113") (name "unconnected-(IC3-(XCK0{slash}AIN0)PE2-Pad4)") (class "Default")
      (node (ref "IC3") (pin "4") (pinfunction "(XCK0/AIN0)PE2_4") (pintype "bidirectional"))
    )
    (net (code "114") (name "unconnected-(IC3-(XCK1)PD5-Pad48)") (class "Default")
      (node (ref "IC3") (pin "48") (pinfunction "(XCK1)PD5_48") (pintype "bidirectional"))
    )
    (net (code "115") (name "unconnected-(IC3-PH2(XCK2)-Pad14)") (class "Default")
      (node (ref "IC3") (pin "14") (pinfunction "PH2(XCK2)_14") (pintype "bidirectional"))
    )
    (net (code "116") (name "unconnected-(IC3-PH7(T4)-Pad27)") (class "Default")
      (node (ref "IC3") (pin "27") (pinfunction "PH7(T4)_27") (pintype "bidirectional"))
    )
    (net (code "117") (name "unconnected-(IC3-PJ2(XCK3{slash}PCINT11)-Pad65)") (class "Default")
      (node (ref "IC3") (pin "65") (pinfunction "PJ2(XCK3/PCINT11)_65") (pintype "bidirectional"))
    )
    (net (code "118") (name "unconnected-(IC3-PJ3(PCINT12)-Pad66)") (class "Default")
      (node (ref "IC3") (pin "66") (pinfunction "PJ3(PCINT12)_66") (pintype "bidirectional"))
    )
    (net (code "119") (name "unconnected-(IC3-PJ4(PCINT13)-Pad67)") (class "Default")
      (node (ref "IC3") (pin "67") (pinfunction "PJ4(PCINT13)_67") (pintype "bidirectional"))
    )
    (net (code "120") (name "unconnected-(IC3-PJ5(PCINT14)-Pad68)") (class "Default")
      (node (ref "IC3") (pin "68") (pinfunction "PJ5(PCINT14)_68") (pintype "bidirectional"))
    )
    (net (code "121") (name "unconnected-(IC3-PJ6(PCINT15)-Pad69)") (class "Default")
      (node (ref "IC3") (pin "69") (pinfunction "PJ6(PCINT15)_69") (pintype "bidirectional"))
    )
    (net (code "122") (name "unconnected-(IC3-PJ7-Pad79)") (class "Default")
      (node (ref "IC3") (pin "79") (pinfunction "PJ7_79") (pintype "bidirectional"))
    )
    (net (code "123") (name "unconnected-(IC3-XTAL1-Pad34)") (class "Default")
      (node (ref "IC3") (pin "34") (pinfunction "XTAL1_34") (pintype "input"))
    )
    (net (code "124") (name "unconnected-(IC4-(AIN0{slash}INT1)PD1-Pad7)") (class "Default")
      (node (ref "IC4") (pin "7") (pinfunction "(AIN0/INT1)PD1_7") (pintype "bidirectional"))
    )
    (net (code "125") (name "unconnected-(IC4-(AIN2{slash}PCINT11)PC2-Pad5)") (class "Default")
      (node (ref "IC4") (pin "5") (pinfunction "(AIN2/PCINT11)PC2_5") (pintype "bidirectional"))
    )
    (net (code "126") (name "unconnected-(IC4-(INT4{slash}ICP1{slash}CLK0)PC7-Pad22)") (class "Default")
      (node (ref "IC4") (pin "22") (pinfunction "(INT4/ICP1/CLK0)PC7_22") (pintype "bidirectional"))
    )
    (net (code "127") (name "unconnected-(IC4-(OC0B{slash}INT0)PD0-Pad6)") (class "Default")
      (node (ref "IC4") (pin "6") (pinfunction "(OC0B/INT0)PD0_6") (pintype "bidirectional"))
    )
    (net (code "128") (name "unconnected-(IC4-(OC1A{slash}PCINT8)PC6-Pad23)") (class "Default")
      (node (ref "IC4") (pin "23") (pinfunction "(OC1A/PCINT8)PC6_23") (pintype "bidirectional"))
    )
    (net (code "129") (name "unconnected-(IC4-(PCINT5)PB5-Pad19)") (class "Default")
      (node (ref "IC4") (pin "19") (pinfunction "(PCINT5)PB5_19") (pintype "bidirectional"))
    )
    (net (code "130") (name "unconnected-(IC4-(PCINT6)PB6-Pad20)") (class "Default")
      (node (ref "IC4") (pin "20") (pinfunction "(PCINT6)PB6_20") (pintype "bidirectional"))
    )
    (net (code "131") (name "unconnected-(IC4-(PCINT7{slash}OC0A{slash}OC1C)PB7-Pad21)") (class "Default")
      (node (ref "IC4") (pin "21") (pinfunction "(PCINT7/OC0A/OC1C)PB7_21") (pintype "bidirectional"))
    )
    (net (code "132") (name "unconnected-(IC4-(PCINT9{slash}OC1B)PC5-Pad25)") (class "Default")
      (node (ref "IC4") (pin "25") (pinfunction "(PCINT9/OC1B)PC5_25") (pintype "bidirectional"))
    )
    (net (code "133") (name "unconnected-(IC4-(PCINT10)PC4-Pad26)") (class "Default")
      (node (ref "IC4") (pin "26") (pinfunction "(PCINT10)PC4_26") (pintype "bidirectional"))
    )
    (net (code "134") (name "unconnected-(IC4-(RTS{slash}AIN5{slash}INT6)PD6-Pad12)") (class "Default")
      (node (ref "IC4") (pin "12") (pinfunction "(RTS/AIN5/INT6)PD6_12") (pintype "bidirectional"))
    )
    (net (code "135") (name "unconnected-(IC4-(SS{slash}PCINT0)PB0-Pad14)") (class "Default")
      (node (ref "IC4") (pin "14") (pinfunction "(SS/PCINT0)PB0_14") (pintype "bidirectional"))
    )
    (net (code "136") (name "unconnected-(IC4-(T1{slash}PCINT4)PB4-Pad18)") (class "Default")
      (node (ref "IC4") (pin "18") (pinfunction "(T1/PCINT4)PB4_18") (pintype "bidirectional"))
    )
    (net (code "137") (name "unconnected-(IC4-XTAL1-Pad1)") (class "Default")
      (node (ref "IC4") (pin "1") (pinfunction "XTAL1_1") (pintype "bidirectional"))
    )
    (net (code "138") (name "unconnected-(IC5A-OUT-Pad1)") (class "Default")
      (node (ref "IC5") (pin "1") (pinfunction "OUT_1") (pintype "output"))
    )
    (net (code "139") (name "unconnected-(IC6-NC{slash}FB-Pad4)") (class "Default")
      (node (ref "IC6") (pin "4") (pinfunction "NC/FB_4") (pintype "passive"))
    )
    (net (code "140") (name "unconnected-(Q1-Pad2)") (class "Default")
      (node (ref "Q1") (pin "2") (pinfunction "2_2") (pintype "passive"))
    )
    (net (code "141") (name "unconnected-(R2-Pad1)") (class "Default")
      (node (ref "R2") (pin "1") (pinfunction "1_1") (pintype "passive"))
    )
    (net (code "142") (name "unconnected-(R3-Pad1)") (class "Default")
      (node (ref "R3") (pin "1") (pinfunction "1_1") (pintype "passive"))
    )
    (net (code "143") (name "unconnected-(R4-Pad1)") (class "Default")
      (node (ref "R4") (pin "1") (pinfunction "1_1") (pintype "passive"))
    )
    (net (code "144") (name "unconnected-(R4-Pad2)") (class "Default")
      (node (ref "R4") (pin "2") (pinfunction "2_2") (pintype "passive"))
    )
    (net (code "145") (name "unconnected-(RN1D-1-Pad4)") (class "Default")
      (node (ref "RN1") (pin "4") (pinfunction "1_4") (pintype "passive"))
    )
    (net (code "146") (name "unconnected-(RN1D-2-Pad5)") (class "Default")
      (node (ref "RN1") (pin "5") (pinfunction "2_5") (pintype "passive"))
    )
    (net (code "147") (name "unconnected-(RN2B-1-Pad2)") (class "Default")
      (node (ref "RN2") (pin "2") (pinfunction "1_2") (pintype "passive"))
    )
    (net (code "148") (name "unconnected-(RN2B-2-Pad7)") (class "Default")
      (node (ref "RN2") (pin "7") (pinfunction "2_7") (pintype "passive"))
    )
    (net (code "149") (name "unconnected-(RN2C-1-Pad3)") (class "Default")
      (node (ref "RN2") (pin "3") (pinfunction "1_3") (pintype "passive"))
    )
    (net (code "150") (name "unconnected-(RN2C-2-Pad6)") (class "Default")
      (node (ref "RN2") (pin "6") (pinfunction "2_6") (pintype "passive"))
    )
    (net (code "151") (name "unconnected-(RN3-Pad1)") (class "Default")
      (node (ref "RN3") (pin "1") (pinfunction "1_1") (pintype "passive"))
    )
    (net (code "152") (name "unconnected-(RN3A-2-Pad8)") (class "Default")
      (node (ref "RN3") (pin "8") (pinfunction "2_8") (pintype "passive"))
    )
    (net (code "153") (name "unconnected-(RN3B-1-Pad2)") (class "Default")
      (node (ref "RN3") (pin "2") (pinfunction "1_2") (pintype "passive"))
    )
    (net (code "154") (name "unconnected-(RN3B-2-Pad7)") (class "Default")
      (node (ref "RN3") (pin "7") (pinfunction "2_7") (pintype "passive"))
    )
    (net (code "155") (name "unconnected-(RN5D-1-Pad4)") (class "Default")
      (node (ref "RN5") (pin "4") (pinfunction "1_4") (pintype "passive"))
    )
    (net (code "156") (name "unconnected-(RN5D-2-Pad5)") (class "Default")
      (node (ref "RN5") (pin "5") (pinfunction "2_5") (pintype "passive"))
    )
    (net (code "157") (name "unconnected-(Y2-Pad3)") (class "Default")
      (node (ref "Y2") (pin "3") (pinfunction "3_3") (pintype "passive"))
    )
  )
)
